# Balance.net
KiCad netlist of a schematic drawn in Altium Designer
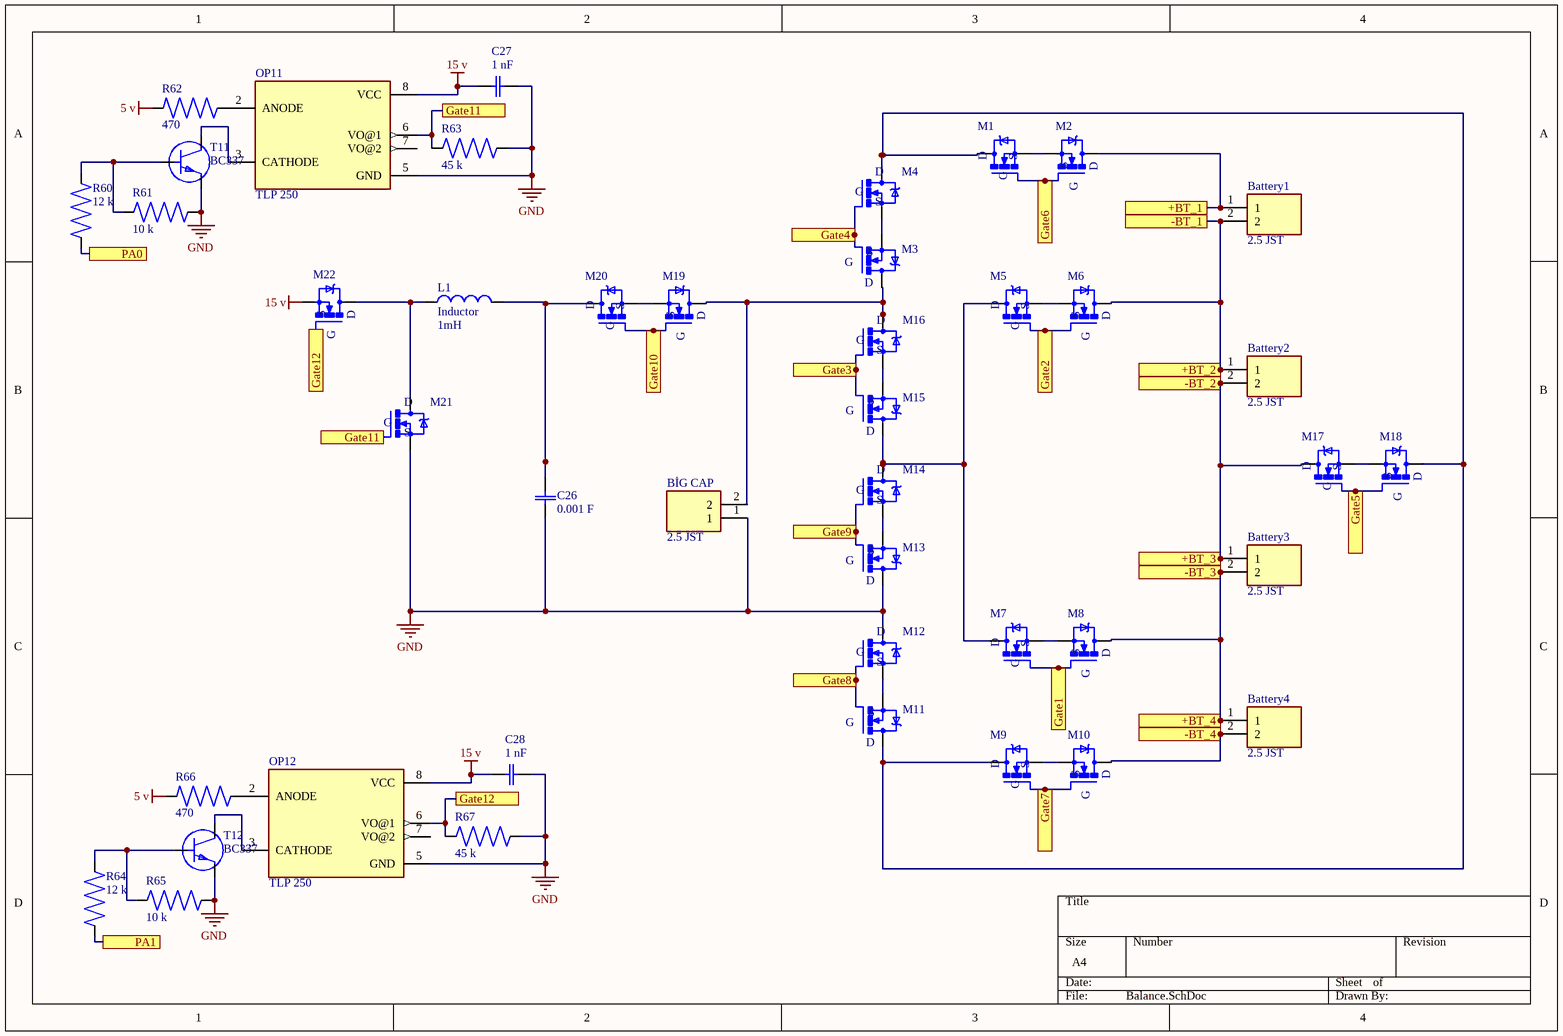
[diagram p0: Balance.SchDoc]

(export (version "E")
  (design (tool "Eeschema 10.0.6"))
  (components
    (comp (ref "Battery1")
      (value "2.5 JST")
      (footprint "2.5 JST")
      (libsource (lib "SSClib1") (part "2.5 JST"))
    )
    (comp (ref "Battery2")
      (value "2.5 JST")
      (footprint "2.5 JST")
      (libsource (lib "SSClib1") (part "2.5 JST"))
    )
    (comp (ref "Battery3")
      (value "2.5 JST")
      (footprint "2.5 JST")
      (libsource (lib "SSClib1") (part "2.5 JST"))
    )
    (comp (ref "Battery4")
      (value "2.5 JST")
      (footprint "2.5 JST")
      (libsource (lib "SSClib1") (part "2.5 JST"))
    )
    (comp (ref "BİG CAP") (value "2.5 JST") (footprint "2.5 JST") (libsource (lib "") (part "2.5 JST_1")))
    (comp (ref "C26") (value "0.001 F") (footprint "0805-c") (libsource (lib "SSClib1") (part "0805-C")))
    (comp (ref "C27") (value "1 nF") (footprint "0805-c") (libsource (lib "SSClib1") (part "0805-C")))
    (comp (ref "C28") (value "1 nF") (footprint "0805-c") (libsource (lib "SSClib1") (part "0805-C")))
    (comp (ref "L1")
      (value "Inductor")
      (footprint "0402-A")
      (fields (field (name "ALTIUM_VALUE") "1mH") (field (name "PUBLISHER") "Altium Limited"))
      (libsource (lib "Miscellaneous Devices") (part "Inductor"))
    )
    (comp (ref "M1") (value "~") (footprint "TO-220") (libsource (lib "") (part "TO-220_1")))
    (comp (ref "M2") (value "~") (footprint "TO-220") (libsource (lib "SSClib1") (part "TO-220")))
    (comp (ref "M3") (value "~") (footprint "TO-220") (libsource (lib "") (part "TO-220_2")))
    (comp (ref "M4") (value "~") (footprint "TO-220") (libsource (lib "SSClib1") (part "TO-220")))
    (comp (ref "M5") (value "~") (footprint "TO-220") (libsource (lib "") (part "TO-220_1")))
    (comp (ref "M6") (value "~") (footprint "TO-220") (libsource (lib "SSClib1") (part "TO-220")))
    (comp (ref "M7") (value "~") (footprint "TO-220") (libsource (lib "") (part "TO-220_1")))
    (comp (ref "M8") (value "~") (footprint "TO-220") (libsource (lib "SSClib1") (part "TO-220")))
    (comp (ref "M9") (value "~") (footprint "TO-220") (libsource (lib "") (part "TO-220_1")))
    (comp (ref "M10") (value "~") (footprint "TO-220") (libsource (lib "SSClib1") (part "TO-220")))
    (comp (ref "M11") (value "~") (footprint "TO-220") (libsource (lib "") (part "TO-220_2")))
    (comp (ref "M12") (value "~") (footprint "TO-220") (libsource (lib "SSClib1") (part "TO-220")))
    (comp (ref "M13") (value "~") (footprint "TO-220") (libsource (lib "") (part "TO-220_2")))
    (comp (ref "M14") (value "~") (footprint "TO-220") (libsource (lib "SSClib1") (part "TO-220")))
    (comp (ref "M15") (value "~") (footprint "TO-220") (libsource (lib "") (part "TO-220_2")))
    (comp (ref "M16") (value "~") (footprint "TO-220") (libsource (lib "SSClib1") (part "TO-220")))
    (comp (ref "M17") (value "~") (footprint "TO-220") (libsource (lib "") (part "TO-220_1")))
    (comp (ref "M18") (value "~") (footprint "TO-220") (libsource (lib "SSClib1") (part "TO-220")))
    (comp (ref "M19") (value "~") (footprint "TO-220") (libsource (lib "SSClib1") (part "TO-220")))
    (comp (ref "M20") (value "~") (footprint "TO-220") (libsource (lib "") (part "TO-220_1")))
    (comp (ref "M21") (value "~") (footprint "TO-220") (libsource (lib "SSClib1") (part "TO-220")))
    (comp (ref "M22") (value "~") (footprint "TO-220") (libsource (lib "SSClib1") (part "TO-220")))
    (comp (ref "OP11") (value "TLP 250") (footprint "TLP 250") (libsource (lib "SSClib1") (part "TLP 250")))
    (comp (ref "OP12") (value "TLP 250") (footprint "TLP 250") (libsource (lib "SSClib1") (part "TLP 250")))
    (comp (ref "R60") (value "12 k") (footprint "10 k") (libsource (lib "SSClib1") (part "10 k")))
    (comp (ref "R61") (value "10 k") (footprint "10 k") (libsource (lib "SSClib1") (part "10 k")))
    (comp (ref "R62") (value "470") (footprint "10 k") (libsource (lib "SSClib1") (part "10 k")))
    (comp (ref "R63") (value "45 k") (footprint "10 k") (libsource (lib "SSClib1") (part "10 k")))
    (comp (ref "R64") (value "12 k") (footprint "10 k") (libsource (lib "SSClib1") (part "10 k")))
    (comp (ref "R65") (value "10 k") (footprint "10 k") (libsource (lib "SSClib1") (part "10 k")))
    (comp (ref "R66") (value "470") (footprint "10 k") (libsource (lib "SSClib1") (part "10 k")))
    (comp (ref "R67") (value "45 k") (footprint "10 k") (libsource (lib "SSClib1") (part "10 k")))
    (comp (ref "T11") (value "BC337") (footprint "BC337") (libsource (lib "SSClib1") (part "BC337")))
    (comp (ref "T12") (value "BC337") (footprint "BC337") (libsource (lib "SSClib1") (part "BC337")))
  )
  (nets
    (net (code "1") (name "/+BT_1") (class "Default")
      (node (ref "Battery1") (pin "1") (pinfunction "1_1") (pintype "passive"))
      (node (ref "M2") (pin "D") (pinfunction "D_D") (pintype "passive"))
    )
    (net (code "2") (name "/+BT_2") (class "Default")
      (node (ref "Battery1") (pin "2") (pinfunction "2_2") (pintype "passive"))
      (node (ref "Battery2") (pin "1") (pinfunction "1_1") (pintype "passive"))
      (node (ref "M6") (pin "D") (pinfunction "D_D") (pintype "passive"))
    )
    (net (code "3") (name "/+BT_3") (class "Default")
      (node (ref "Battery2") (pin "2") (pinfunction "2_2") (pintype "passive"))
      (node (ref "Battery3") (pin "1") (pinfunction "1_1") (pintype "passive"))
      (node (ref "M17") (pin "D") (pinfunction "D_D") (pintype "passive"))
    )
    (net (code "4") (name "/+BT_4") (class "Default")
      (node (ref "Battery3") (pin "2") (pinfunction "2_2") (pintype "passive"))
      (node (ref "Battery4") (pin "1") (pinfunction "1_1") (pintype "passive"))
      (node (ref "M8") (pin "D") (pinfunction "D_D") (pintype "passive"))
    )
    (net (code "5") (name "/-BT_4") (class "Default")
      (node (ref "Battery4") (pin "2") (pinfunction "2_2") (pintype "passive"))
      (node (ref "M10") (pin "D") (pinfunction "D_D") (pintype "passive"))
    )
    (net (code "6") (name "/Gate1") (class "Default")
      (node (ref "M7") (pin "G") (pinfunction "G_G") (pintype "passive"))
      (node (ref "M8") (pin "G") (pinfunction "G_G") (pintype "passive"))
    )
    (net (code "7") (name "/Gate2") (class "Default")
      (node (ref "M5") (pin "G") (pinfunction "G_G") (pintype "passive"))
      (node (ref "M6") (pin "G") (pinfunction "G_G") (pintype "passive"))
    )
    (net (code "8") (name "/Gate3") (class "Default")
      (node (ref "M15") (pin "G") (pinfunction "G_G") (pintype "passive"))
      (node (ref "M16") (pin "G") (pinfunction "G_G") (pintype "passive"))
    )
    (net (code "9") (name "/Gate4") (class "Default")
      (node (ref "M3") (pin "G") (pinfunction "G_G") (pintype "passive"))
      (node (ref "M4") (pin "G") (pinfunction "G_G") (pintype "passive"))
    )
    (net (code "10") (name "/Gate5") (class "Default")
      (node (ref "M17") (pin "G") (pinfunction "G_G") (pintype "passive"))
      (node (ref "M18") (pin "G") (pinfunction "G_G") (pintype "passive"))
    )
    (net (code "11") (name "/Gate6") (class "Default")
      (node (ref "M1") (pin "G") (pinfunction "G_G") (pintype "passive"))
      (node (ref "M2") (pin "G") (pinfunction "G_G") (pintype "passive"))
    )
    (net (code "12") (name "/Gate7") (class "Default")
      (node (ref "M10") (pin "G") (pinfunction "G_G") (pintype "passive"))
      (node (ref "M9") (pin "G") (pinfunction "G_G") (pintype "passive"))
    )
    (net (code "13") (name "/Gate8") (class "Default")
      (node (ref "M11") (pin "G") (pinfunction "G_G") (pintype "passive"))
      (node (ref "M12") (pin "G") (pinfunction "G_G") (pintype "passive"))
    )
    (net (code "14") (name "/Gate9") (class "Default")
      (node (ref "M13") (pin "G") (pinfunction "G_G") (pintype "passive"))
      (node (ref "M14") (pin "G") (pinfunction "G_G") (pintype "passive"))
    )
    (net (code "15") (name "/Gate10") (class "Default")
      (node (ref "M19") (pin "G") (pinfunction "G_G") (pintype "passive"))
      (node (ref "M20") (pin "G") (pinfunction "G_G") (pintype "passive"))
    )
    (net (code "16") (name "/Gate11") (class "Default")
      (node (ref "M21") (pin "G") (pinfunction "G_G") (pintype "passive"))
      (node (ref "OP11") (pin "6") (pinfunction "VO@1_6") (pintype "output"))
      (node (ref "R63") (pin "2") (pinfunction "2_2") (pintype "passive"))
    )
    (net (code "17") (name "/Gate12") (class "Default")
      (node (ref "M22") (pin "G") (pinfunction "G_G") (pintype "passive"))
      (node (ref "OP12") (pin "6") (pinfunction "VO@1_6") (pintype "output"))
      (node (ref "R67") (pin "2") (pinfunction "2_2") (pintype "passive"))
    )
    (net (code "18") (name "/PA0") (class "Default")
      (node (ref "R60") (pin "2") (pinfunction "2_2") (pintype "passive"))
    )
    (net (code "19") (name "/PA1") (class "Default")
      (node (ref "R64") (pin "2") (pinfunction "2_2") (pintype "passive"))
    )
    (net (code "20") (name "5 v") (class "Default")
      (node (ref "R62") (pin "1") (pinfunction "1_1") (pintype "passive"))
      (node (ref "R66") (pin "1") (pinfunction "1_1") (pintype "passive"))
    )
    (net (code "21") (name "15 v") (class "Default")
      (node (ref "C27") (pin "1") (pinfunction "C1_1") (pintype "passive"))
      (node (ref "C28") (pin "1") (pinfunction "C1_1") (pintype "passive"))
      (node (ref "M22") (pin "S") (pinfunction "S_S") (pintype "passive"))
      (node (ref "OP11") (pin "8") (pinfunction "VCC_8") (pintype "power_in"))
      (node (ref "OP12") (pin "8") (pinfunction "VCC_8") (pintype "power_in"))
    )
    (net (code "22") (name "GND") (class "Default")
      (node (ref "BİG CAP") (pin "1") (pinfunction "1_1") (pintype "passive"))
      (node (ref "C26") (pin "1") (pinfunction "C1_1") (pintype "passive"))
      (node (ref "C27") (pin "2") (pinfunction "C2_2") (pintype "passive"))
      (node (ref "C28") (pin "2") (pinfunction "C2_2") (pintype "passive"))
      (node (ref "M12") (pin "D") (pinfunction "D_D") (pintype "passive"))
      (node (ref "M13") (pin "D") (pinfunction "D_D") (pintype "passive"))
      (node (ref "M21") (pin "S") (pinfunction "S_S") (pintype "passive"))
      (node (ref "OP11") (pin "5") (pinfunction "GND_5") (pintype "power_in"))
      (node (ref "OP12") (pin "5") (pinfunction "GND_5") (pintype "power_in"))
      (node (ref "R61") (pin "1") (pinfunction "1_1") (pintype "passive"))
      (node (ref "R63") (pin "1") (pinfunction "1_1") (pintype "passive"))
      (node (ref "R65") (pin "1") (pinfunction "1_1") (pintype "passive"))
      (node (ref "R67") (pin "1") (pinfunction "1_1") (pintype "passive"))
      (node (ref "T11") (pin "1") (pinfunction "E_1") (pintype "passive"))
      (node (ref "T12") (pin "1") (pinfunction "E_1") (pintype "passive"))
    )
    (net (code "23") (name "Net-(BİG CAP-Pad2)") (class "Default")
      (node (ref "BİG CAP") (pin "2") (pinfunction "2_2") (pintype "passive"))
      (node (ref "M16") (pin "D") (pinfunction "D_D") (pintype "passive"))
      (node (ref "M19") (pin "D") (pinfunction "D_D") (pintype "passive"))
      (node (ref "M3") (pin "D") (pinfunction "D_D") (pintype "passive"))
    )
    (net (code "24") (name "Net-(C26-C2)") (class "Default")
      (node (ref "C26") (pin "2") (pinfunction "C2_2") (pintype "passive"))
      (node (ref "L1") (pin "2") (pinfunction "2_2") (pintype "passive"))
      (node (ref "M20") (pin "D") (pinfunction "D_D") (pintype "passive"))
    )
    (net (code "25") (name "Net-(L1-Pad1)") (class "Default")
      (node (ref "L1") (pin "1") (pinfunction "1_1") (pintype "passive"))
      (node (ref "M21") (pin "D") (pinfunction "D_D") (pintype "passive"))
      (node (ref "M22") (pin "D") (pinfunction "D_D") (pintype "passive"))
    )
    (net (code "26") (name "Net-(M1-PadD)") (class "Default")
      (node (ref "M1") (pin "D") (pinfunction "D_D") (pintype "passive"))
      (node (ref "M11") (pin "D") (pinfunction "D_D") (pintype "passive"))
      (node (ref "M18") (pin "D") (pinfunction "D_D") (pintype "passive"))
      (node (ref "M4") (pin "D") (pinfunction "D_D") (pintype "passive"))
      (node (ref "M9") (pin "D") (pinfunction "D_D") (pintype "passive"))
    )
    (net (code "27") (name "Net-(M1-PadS)") (class "Default")
      (node (ref "M1") (pin "S") (pinfunction "S_S") (pintype "passive"))
      (node (ref "M2") (pin "S") (pinfunction "S_S") (pintype "passive"))
    )
    (net (code "28") (name "Net-(M3-PadS)") (class "Default")
      (node (ref "M3") (pin "S") (pinfunction "S_S") (pintype "passive"))
      (node (ref "M4") (pin "S") (pinfunction "S_S") (pintype "passive"))
    )
    (net (code "29") (name "Net-(M5-PadS)") (class "Default")
      (node (ref "M5") (pin "S") (pinfunction "S_S") (pintype "passive"))
      (node (ref "M6") (pin "S") (pinfunction "S_S") (pintype "passive"))
    )
    (net (code "30") (name "Net-(M7-PadS)") (class "Default")
      (node (ref "M7") (pin "S") (pinfunction "S_S") (pintype "passive"))
      (node (ref "M8") (pin "S") (pinfunction "S_S") (pintype "passive"))
    )
    (net (code "31") (name "Net-(M10-PadS)") (class "Default")
      (node (ref "M10") (pin "S") (pinfunction "S_S") (pintype "passive"))
      (node (ref "M9") (pin "S") (pinfunction "S_S") (pintype "passive"))
    )
    (net (code "32") (name "Net-(M11-PadS)") (class "Default")
      (node (ref "M11") (pin "S") (pinfunction "S_S") (pintype "passive"))
      (node (ref "M12") (pin "S") (pinfunction "S_S") (pintype "passive"))
    )
    (net (code "33") (name "Net-(M13-PadS)") (class "Default")
      (node (ref "M13") (pin "S") (pinfunction "S_S") (pintype "passive"))
      (node (ref "M14") (pin "S") (pinfunction "S_S") (pintype "passive"))
    )
    (net (code "34") (name "Net-(M14-PadD)") (class "Default")
      (node (ref "M14") (pin "D") (pinfunction "D_D") (pintype "passive"))
      (node (ref "M15") (pin "D") (pinfunction "D_D") (pintype "passive"))
      (node (ref "M5") (pin "D") (pinfunction "D_D") (pintype "passive"))
      (node (ref "M7") (pin "D") (pinfunction "D_D") (pintype "passive"))
    )
    (net (code "35") (name "Net-(M15-PadS)") (class "Default")
      (node (ref "M15") (pin "S") (pinfunction "S_S") (pintype "passive"))
      (node (ref "M16") (pin "S") (pinfunction "S_S") (pintype "passive"))
    )
    (net (code "36") (name "Net-(M17-PadS)") (class "Default")
      (node (ref "M17") (pin "S") (pinfunction "S_S") (pintype "passive"))
      (node (ref "M18") (pin "S") (pinfunction "S_S") (pintype "passive"))
    )
    (net (code "37") (name "Net-(M19-PadS)") (class "Default")
      (node (ref "M19") (pin "S") (pinfunction "S_S") (pintype "passive"))
      (node (ref "M20") (pin "S") (pinfunction "S_S") (pintype "passive"))
    )
    (net (code "38") (name "Net-(OP11-ANODE)") (class "Default")
      (node (ref "OP11") (pin "2") (pinfunction "ANODE_2") (pintype "passive"))
      (node (ref "R62") (pin "2") (pinfunction "2_2") (pintype "passive"))
    )
    (net (code "39") (name "Net-(OP11-CATHODE)") (class "Default")
      (node (ref "OP11") (pin "3") (pinfunction "CATHODE_3") (pintype "passive"))
      (node (ref "T11") (pin "3") (pinfunction "C_3") (pintype "passive"))
    )
    (net (code "40") (name "Net-(OP12-ANODE)") (class "Default")
      (node (ref "OP12") (pin "2") (pinfunction "ANODE_2") (pintype "passive"))
      (node (ref "R66") (pin "2") (pinfunction "2_2") (pintype "passive"))
    )
    (net (code "41") (name "Net-(OP12-CATHODE)") (class "Default")
      (node (ref "OP12") (pin "3") (pinfunction "CATHODE_3") (pintype "passive"))
      (node (ref "T12") (pin "3") (pinfunction "C_3") (pintype "passive"))
    )
    (net (code "42") (name "Net-(T11-B)") (class "Default")
      (node (ref "R60") (pin "1") (pinfunction "1_1") (pintype "passive"))
      (node (ref "R61") (pin "2") (pinfunction "2_2") (pintype "passive"))
      (node (ref "T11") (pin "2") (pinfunction "B_2") (pintype "passive"))
    )
    (net (code "43") (name "Net-(T12-B)") (class "Default")
      (node (ref "R64") (pin "1") (pinfunction "1_1") (pintype "passive"))
      (node (ref "R65") (pin "2") (pinfunction "2_2") (pintype "passive"))
      (node (ref "T12") (pin "2") (pinfunction "B_2") (pintype "passive"))
    )
    (net (code "44") (name "unconnected-(OP11-VO@2-Pad7)") (class "Default")
      (node (ref "OP11") (pin "7") (pinfunction "VO@2_7") (pintype "output"))
    )
    (net (code "45") (name "unconnected-(OP12-VO@2-Pad7)") (class "Default")
      (node (ref "OP12") (pin "7") (pinfunction "VO@2_7") (pintype "output"))
    )
  )
)
